# main.net
KiCad netlist of a schematic drawn in Altium Designer
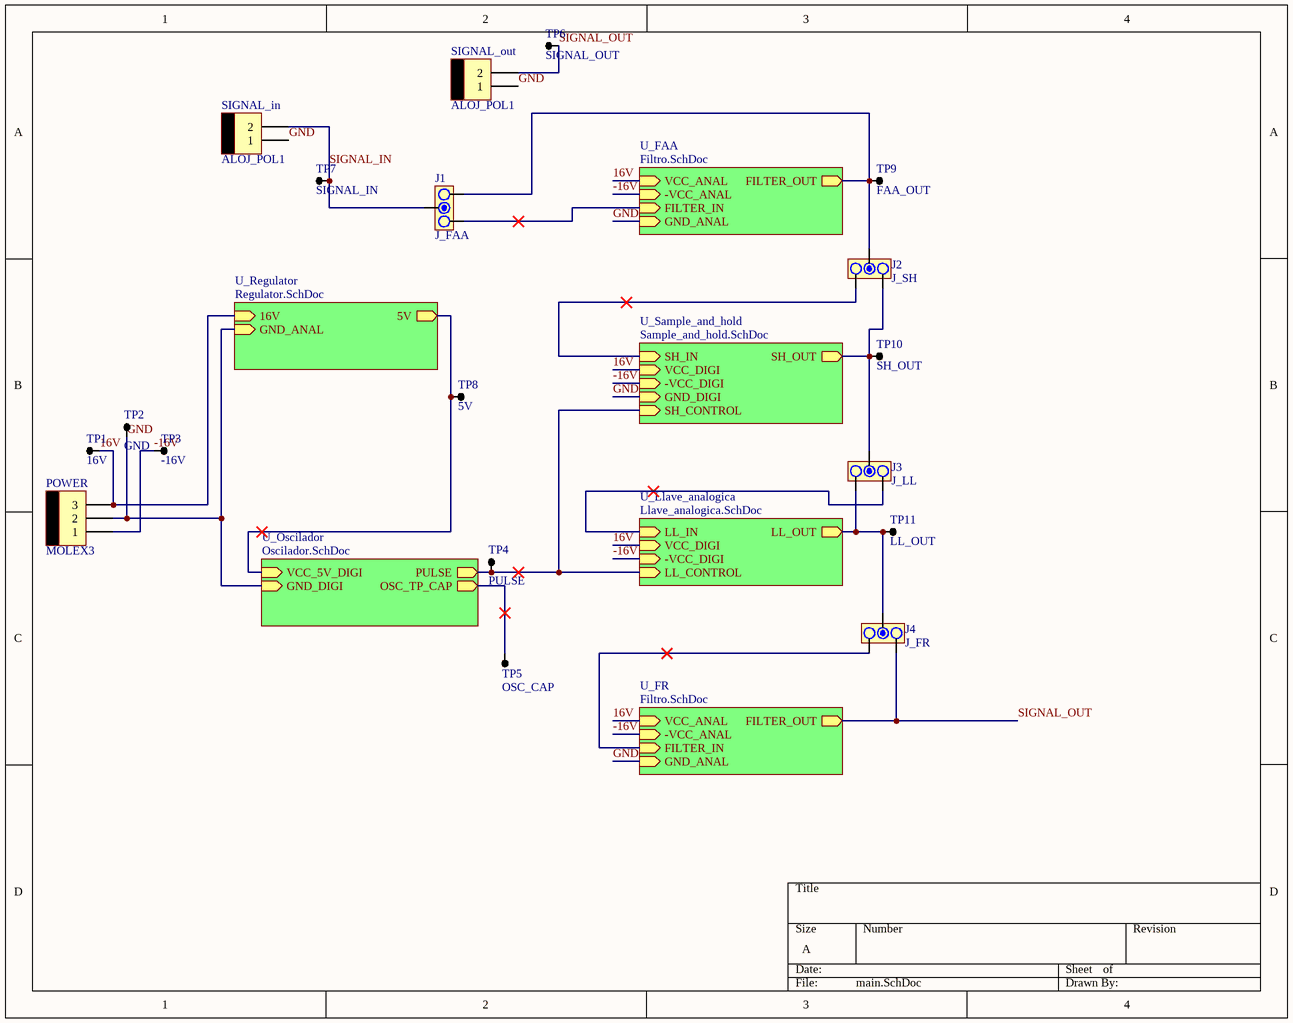
[diagram p0: main.SchDoc]

(export (version "E")
  (design (tool "Eeschema 10.0.6"))
  (components
    (comp (ref "J1") (value "J_FAA") (footprint "JUMPER3") (libsource (lib "") (part "JUMPER3_1")))
    (comp (ref "J2") (value "J_SH") (footprint "JUMPER3") (libsource (lib "LIB PIO IX") (part "JUMPER3")))
    (comp (ref "J3") (value "J_LL") (footprint "JUMPER3") (libsource (lib "LIB PIO IX") (part "JUMPER3")))
    (comp (ref "J4") (value "J_FR") (footprint "JUMPER3") (libsource (lib "LIB PIO IX") (part "JUMPER3")))
    (comp (ref "POWER") (value "MOLEX3") (footprint "MOLEX3") (libsource (lib "LIB PIO IX") (part "MOLEX3")))
    (comp (ref "SIGNAL_in")
      (value "ALOJ_POL1")
      (footprint "MOLEX2")
      (libsource (lib "LIB PIO IX") (part "MOLEX2"))
    )
    (comp (ref "SIGNAL_out")
      (value "ALOJ_POL1")
      (footprint "MOLEX2")
      (libsource (lib "LIB PIO IX") (part "MOLEX2"))
    )
    (comp (ref "TP1") (value "16V") (footprint "TPTH") (libsource (lib "LIB PIO IX") (part "TP")))
    (comp (ref "TP2") (value "GND") (footprint "TPTH") (libsource (lib "LIB PIO IX") (part "TP")))
    (comp (ref "TP3") (value "-16V") (footprint "TPTH") (libsource (lib "LIB PIO IX") (part "TP")))
    (comp (ref "TP4") (value "PULSE") (footprint "TPTH") (libsource (lib "LIB PIO IX") (part "TP")))
    (comp (ref "TP5") (value "OSC_CAP") (footprint "TPTH") (libsource (lib "LIB PIO IX") (part "TP")))
    (comp (ref "TP6") (value "SIGNAL_OUT") (footprint "TPTH") (libsource (lib "LIB PIO IX") (part "TP")))
    (comp (ref "TP7") (value "SIGNAL_IN") (footprint "TPTH") (libsource (lib "LIB PIO IX") (part "TP")))
    (comp (ref "TP8") (value "5V") (footprint "TPTH") (libsource (lib "LIB PIO IX") (part "TP")))
    (comp (ref "TP9") (value "FAA_OUT") (footprint "TPTH") (libsource (lib "LIB PIO IX") (part "TP")))
    (comp (ref "TP10") (value "SH_OUT") (footprint "TPTH") (libsource (lib "LIB PIO IX") (part "TP")))
    (comp (ref "TP11") (value "LL_OUT") (footprint "TPTH") (libsource (lib "LIB PIO IX") (part "TP")))
  )
  (nets
    (net (code "1") (name "/-16V") (class "Default")
      (node (ref "POWER") (pin "1") (pinfunction "1_1") (pintype "passive"))
      (node (ref "TP3") (pin "1") (pinfunction "1_1") (pintype "passive"))
    )
    (net (code "2") (name "/5V") (class "Default")
      (node (ref "TP8") (pin "1") (pinfunction "1_1") (pintype "passive"))
    )
    (net (code "3") (name "/16V") (class "Default")
      (node (ref "POWER") (pin "3") (pinfunction "3_3") (pintype "passive"))
      (node (ref "TP1") (pin "1") (pinfunction "1_1") (pintype "passive"))
    )
    (net (code "4") (name "/FILTER_IN") (class "Default")
      (node (ref "J4") (pin "3") (pinfunction "3_3") (pintype "passive"))
    )
    (net (code "5") (name "/FILTER_IN_1") (class "Default")
      (node (ref "J1") (pin "3") (pinfunction "3_3") (pintype "passive"))
    )
    (net (code "6") (name "/FILTER_OUT") (class "Default")
      (node (ref "J1") (pin "1") (pinfunction "1_1") (pintype "passive"))
      (node (ref "J2") (pin "2") (pinfunction "2_2") (pintype "passive"))
      (node (ref "TP9") (pin "1") (pinfunction "1_1") (pintype "passive"))
    )
    (net (code "7") (name "/GND") (class "Default")
      (node (ref "POWER") (pin "2") (pinfunction "2_2") (pintype "passive"))
      (node (ref "SIGNAL_in") (pin "1") (pinfunction "1_1") (pintype "passive"))
      (node (ref "SIGNAL_out") (pin "1") (pinfunction "1_1") (pintype "passive"))
      (node (ref "TP2") (pin "1") (pinfunction "1_1") (pintype "passive"))
    )
    (net (code "8") (name "/LL_IN") (class "Default")
      (node (ref "J3") (pin "1") (pinfunction "1_1") (pintype "passive"))
    )
    (net (code "9") (name "/LL_OUT") (class "Default")
      (node (ref "J3") (pin "3") (pinfunction "3_3") (pintype "passive"))
      (node (ref "J4") (pin "2") (pinfunction "2_2") (pintype "passive"))
      (node (ref "TP11") (pin "1") (pinfunction "1_1") (pintype "passive"))
    )
    (net (code "10") (name "/OSC_TP_CAP") (class "Default")
      (node (ref "TP5") (pin "1") (pinfunction "1_1") (pintype "passive"))
    )
    (net (code "11") (name "/PULSE") (class "Default")
      (node (ref "TP4") (pin "1") (pinfunction "1_1") (pintype "passive"))
    )
    (net (code "12") (name "/SH_IN") (class "Default")
      (node (ref "J2") (pin "3") (pinfunction "3_3") (pintype "passive"))
    )
    (net (code "13") (name "/SH_OUT") (class "Default")
      (node (ref "J2") (pin "1") (pinfunction "1_1") (pintype "passive"))
      (node (ref "J3") (pin "2") (pinfunction "2_2") (pintype "passive"))
      (node (ref "TP10") (pin "1") (pinfunction "1_1") (pintype "passive"))
    )
    (net (code "14") (name "/SIGNAL_IN") (class "Default")
      (node (ref "J1") (pin "2") (pinfunction "2_2") (pintype "passive"))
      (node (ref "SIGNAL_in") (pin "2") (pinfunction "2_2") (pintype "passive"))
      (node (ref "TP7") (pin "1") (pinfunction "1_1") (pintype "passive"))
    )
    (net (code "15") (name "/SIGNAL_OUT") (class "Default")
      (node (ref "J4") (pin "1") (pinfunction "1_1") (pintype "passive"))
      (node (ref "SIGNAL_out") (pin "2") (pinfunction "2_2") (pintype "passive"))
      (node (ref "TP6") (pin "1") (pinfunction "1_1") (pintype "passive"))
    )
  )
)
